# HV_Measurements.net
KiCad netlist of a schematic drawn in Altium Designer
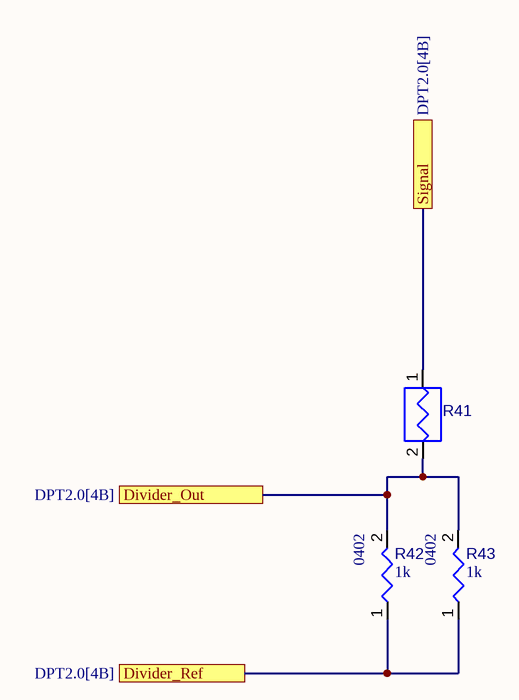
[diagram p0: HV_Measurements.SchDoc]

(export (version "E")
  (design (tool "Eeschema 10.0.6"))
  (components
    (comp (ref "R41")
      (value "RES-2512-SIDE")
      (footprint "RES_2512_SIDE")
      (description "SMD Resistor - 2512 (6432) On It's Side")
      (libsource (lib "2256-GaN Power") (part "RES-SIDE-2"))
    )
    (comp (ref "R42")
      (value "1k")
      (footprint "RES_0402_HIGH")
      (description "SMD Resistor - 0402 (1005 Metric)")
      (fields (field (name "Comment") "RES-0402"))
      (libsource (lib "2256-GaN Power") (part "RES-2"))
    )
    (comp (ref "R43")
      (value "1k")
      (footprint "RES_0402_HIGH")
      (description "SMD Resistor - 0402 (1005 Metric)")
      (fields (field (name "Comment") "RES-0402"))
      (libsource (lib "2256-GaN Power") (part "RES-2"))
    )
  )
  (nets
    (net (code "1") (name "/Divider_Out") (class "Default")
      (node (ref "R41") (pin "2") (pinfunction "2_2") (pintype "passive"))
      (node (ref "R42") (pin "2") (pinfunction "2_2") (pintype "passive"))
      (node (ref "R43") (pin "2") (pinfunction "2_2") (pintype "passive"))
    )
    (net (code "2") (name "/Divider_Ref") (class "Default")
      (node (ref "R42") (pin "1") (pinfunction "1_1") (pintype "passive"))
      (node (ref "R43") (pin "1") (pinfunction "1_1") (pintype "passive"))
    )
    (net (code "3") (name "/Signal") (class "Default")
      (node (ref "R41") (pin "1") (pinfunction "1_1") (pintype "passive"))
    )
  )
)
